# phase_and_amplifier_ssb.net
KiCad netlist of a schematic drawn in EAGLE
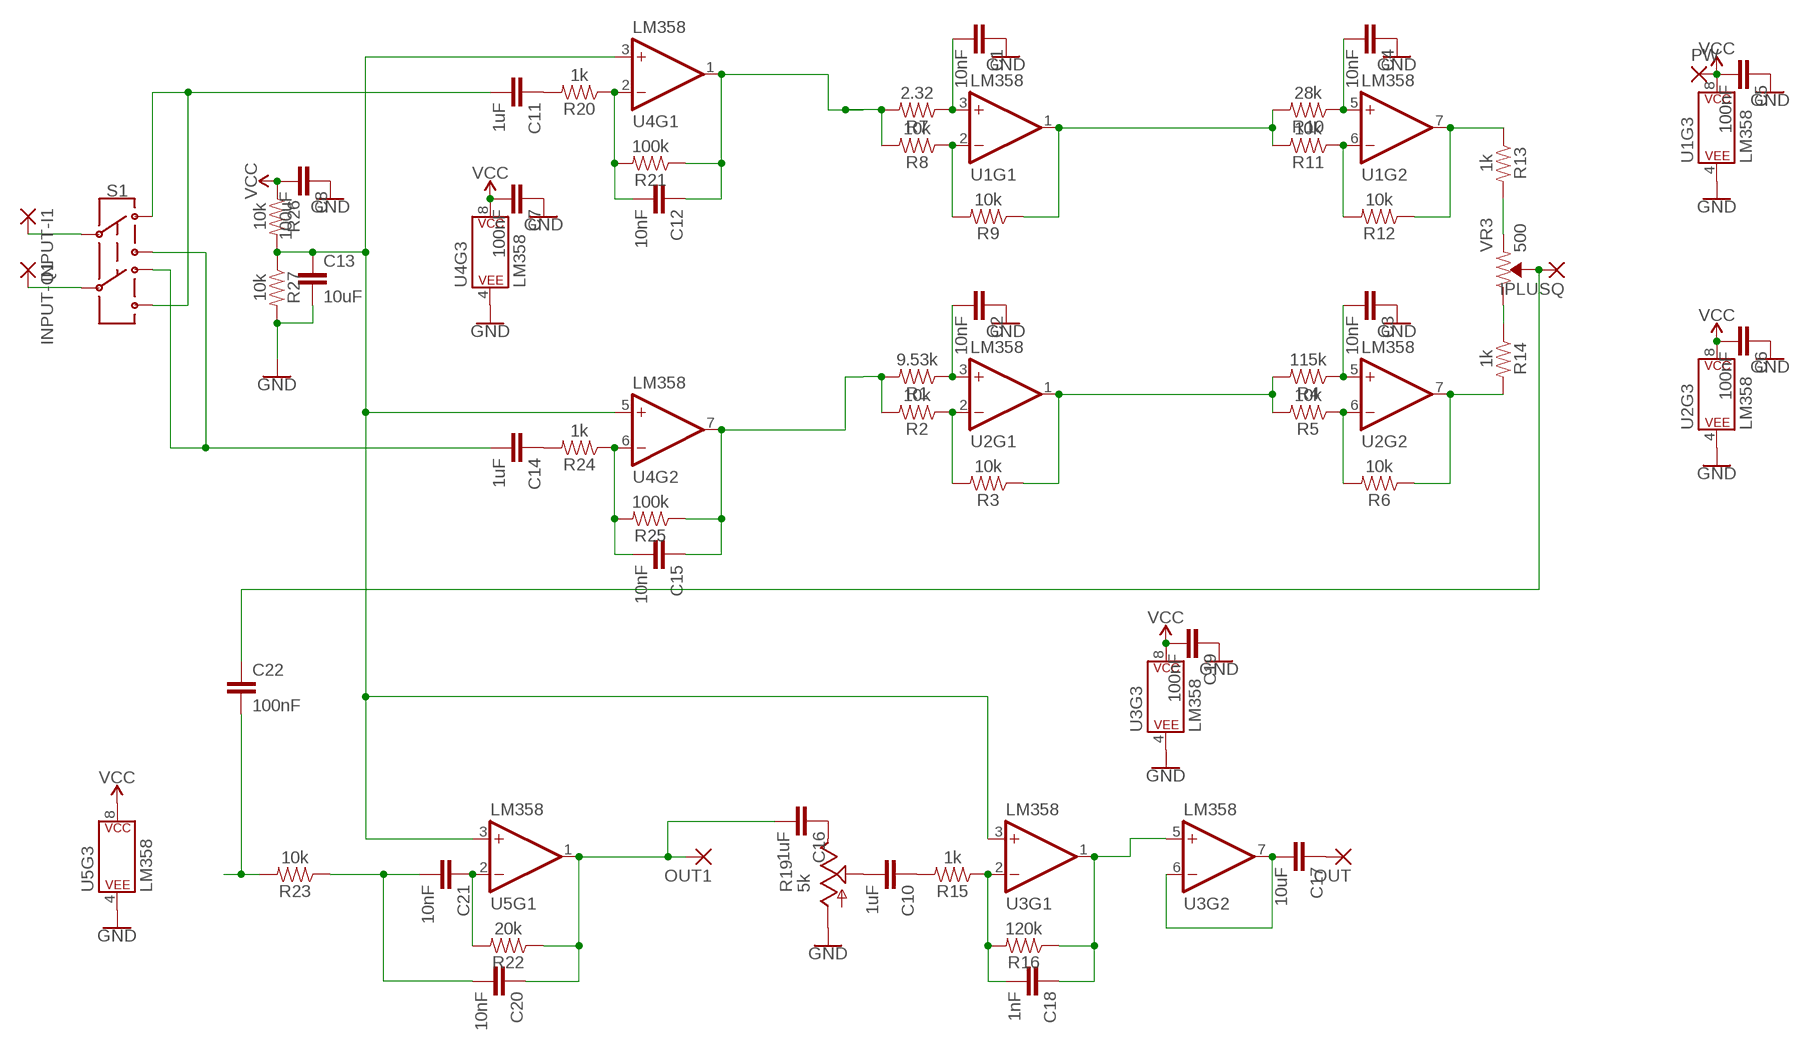
[diagram p0: schematic, sheet 1]

(export (version "E")
  (design (tool "Eeschema 10.0.6"))
  (components
    (comp (ref "C1")
      (value "10nF")
      (footprint "eagle-import:C5B3.5")
      (libsource (lib "eagle-import") (part "C5/3.5"))
    )
    (comp (ref "C2")
      (value "10nF")
      (footprint "eagle-import:C5B3.5")
      (libsource (lib "eagle-import") (part "C5/3.5"))
    )
    (comp (ref "C3")
      (value "10nF")
      (footprint "eagle-import:C5B3.5")
      (libsource (lib "eagle-import") (part "C5/3.5"))
    )
    (comp (ref "C4")
      (value "10nF")
      (footprint "eagle-import:C5B3.5")
      (libsource (lib "eagle-import") (part "C5/3.5"))
    )
    (comp (ref "C5")
      (value "100nF")
      (footprint "eagle-import:C5B3.5")
      (libsource (lib "eagle-import") (part "C5/3.5"))
    )
    (comp (ref "C6")
      (value "100nF")
      (footprint "eagle-import:C5B3.5")
      (libsource (lib "eagle-import") (part "C5/3.5"))
    )
    (comp (ref "C7")
      (value "100nF")
      (footprint "eagle-import:C5B3.5")
      (libsource (lib "eagle-import") (part "C5/3.5"))
    )
    (comp (ref "C8")
      (value "100uF")
      (footprint "eagle-import:C5B3.5")
      (libsource (lib "eagle-import") (part "C5/3.5"))
    )
    (comp (ref "C10")
      (value "1uF")
      (footprint "eagle-import:C5B3.5")
      (libsource (lib "eagle-import") (part "C5/3.5"))
    )
    (comp (ref "C11")
      (value "1uF")
      (footprint "eagle-import:C5B3.5")
      (libsource (lib "eagle-import") (part "C5/3.5"))
    )
    (comp (ref "C12")
      (value "10nF")
      (footprint "eagle-import:C5B3.5")
      (libsource (lib "eagle-import") (part "C5/3.5"))
    )
    (comp (ref "C13")
      (value "10uF")
      (footprint "eagle-import:C5B3.5")
      (libsource (lib "eagle-import") (part "C5/3.5"))
    )
    (comp (ref "C14")
      (value "1uF")
      (footprint "eagle-import:C5B3.5")
      (libsource (lib "eagle-import") (part "C5/3.5"))
    )
    (comp (ref "C15")
      (value "10nF")
      (footprint "eagle-import:C5B3.5")
      (libsource (lib "eagle-import") (part "C5/3.5"))
    )
    (comp (ref "C16")
      (value "1uF")
      (footprint "eagle-import:C5B3.5")
      (libsource (lib "eagle-import") (part "C5/3.5"))
    )
    (comp (ref "C17")
      (value "10uF")
      (footprint "eagle-import:C5B3.5")
      (libsource (lib "eagle-import") (part "C5/3.5"))
    )
    (comp (ref "C18")
      (value "1nF")
      (footprint "eagle-import:C5B3.5")
      (libsource (lib "eagle-import") (part "C5/3.5"))
    )
    (comp (ref "C19")
      (value "100nF")
      (footprint "eagle-import:C5B3.5")
      (libsource (lib "eagle-import") (part "C5/3.5"))
    )
    (comp (ref "C20")
      (value "10nF")
      (footprint "eagle-import:C5B3.5")
      (libsource (lib "eagle-import") (part "C5/3.5"))
    )
    (comp (ref "C21")
      (value "10nF")
      (footprint "eagle-import:C5B3.5")
      (libsource (lib "eagle-import") (part "C5/3.5"))
    )
    (comp (ref "C22")
      (value "100nF")
      (footprint "eagle-import:C5B3.5")
      (libsource (lib "eagle-import") (part "C5/3.5"))
    )
    (comp (ref "INPUT-I1")
      (value "2,54/1,1")
      (footprint "eagle-import:2,54_1,1")
      (libsource (lib "eagle-import") (part "2,54/1,1"))
    )
    (comp (ref "INPUT-Q1")
      (value "2,54/1,1")
      (footprint "eagle-import:2,54_1,1")
      (libsource (lib "eagle-import") (part "2,54/1,1"))
    )
    (comp (ref "IPLUSQ")
      (value "2,54/1,1")
      (footprint "eagle-import:2,54_1,1")
      (libsource (lib "eagle-import") (part "2,54/1,1"))
    )
    (comp (ref "OUT")
      (value "2,54/1,1")
      (footprint "eagle-import:2,54_1,1")
      (libsource (lib "eagle-import") (part "2,54/1,1"))
    )
    (comp (ref "OUT1")
      (value "2,54/1,1")
      (footprint "eagle-import:2,54_1,1")
      (libsource (lib "eagle-import") (part "2,54/1,1"))
    )
    (comp (ref "PW")
      (value "2,54/1,1")
      (footprint "eagle-import:2,54_1,1")
      (libsource (lib "eagle-import") (part "2,54/1,1"))
    )
    (comp (ref "R1")
      (value "9.53k")
      (footprint "eagle-import:AXIAL-0.3")
      (libsource (lib "eagle-import") (part "1KOHM-HORIZ-1/4W-1%"))
    )
    (comp (ref "R2")
      (value "10k")
      (footprint "eagle-import:AXIAL-0.3")
      (libsource (lib "eagle-import") (part "1KOHM-HORIZ-1/4W-1%"))
    )
    (comp (ref "R3")
      (value "10k")
      (footprint "eagle-import:AXIAL-0.3")
      (libsource (lib "eagle-import") (part "1KOHM-HORIZ-1/4W-1%"))
    )
    (comp (ref "R4")
      (value "115k")
      (footprint "eagle-import:AXIAL-0.3")
      (libsource (lib "eagle-import") (part "1KOHM-HORIZ-1/4W-1%"))
    )
    (comp (ref "R5")
      (value "10k")
      (footprint "eagle-import:AXIAL-0.3")
      (libsource (lib "eagle-import") (part "1KOHM-HORIZ-1/4W-1%"))
    )
    (comp (ref "R6")
      (value "10k")
      (footprint "eagle-import:AXIAL-0.3")
      (libsource (lib "eagle-import") (part "1KOHM-HORIZ-1/4W-1%"))
    )
    (comp (ref "R7")
      (value "2.32")
      (footprint "eagle-import:AXIAL-0.3")
      (libsource (lib "eagle-import") (part "1KOHM-HORIZ-1/4W-1%"))
    )
    (comp (ref "R8")
      (value "10k")
      (footprint "eagle-import:AXIAL-0.3")
      (libsource (lib "eagle-import") (part "1KOHM-HORIZ-1/4W-1%"))
    )
    (comp (ref "R9")
      (value "10k")
      (footprint "eagle-import:AXIAL-0.3")
      (libsource (lib "eagle-import") (part "1KOHM-HORIZ-1/4W-1%"))
    )
    (comp (ref "R10")
      (value "28k")
      (footprint "eagle-import:AXIAL-0.3")
      (libsource (lib "eagle-import") (part "1KOHM-HORIZ-1/4W-1%"))
    )
    (comp (ref "R11")
      (value "10k")
      (footprint "eagle-import:AXIAL-0.3")
      (libsource (lib "eagle-import") (part "1KOHM-HORIZ-1/4W-1%"))
    )
    (comp (ref "R12")
      (value "10k")
      (footprint "eagle-import:AXIAL-0.3")
      (libsource (lib "eagle-import") (part "1KOHM-HORIZ-1/4W-1%"))
    )
    (comp (ref "R13")
      (value "1k")
      (footprint "eagle-import:AXIAL-0.3")
      (libsource (lib "eagle-import") (part "1KOHM-HORIZ-1/4W-1%"))
    )
    (comp (ref "R14")
      (value "1k")
      (footprint "eagle-import:AXIAL-0.3")
      (libsource (lib "eagle-import") (part "1KOHM-HORIZ-1/4W-1%"))
    )
    (comp (ref "R15")
      (value "1k")
      (footprint "eagle-import:AXIAL-0.3")
      (libsource (lib "eagle-import") (part "1KOHM-HORIZ-1/4W-1%"))
    )
    (comp (ref "R16")
      (value "120k")
      (footprint "eagle-import:AXIAL-0.3")
      (libsource (lib "eagle-import") (part "1KOHM-HORIZ-1/4W-1%"))
    )
    (comp (ref "R19")
      (value "5k")
      (footprint "eagle-import:B25V")
      (libsource (lib "eagle-import") (part "TRIM_US-B25V"))
    )
    (comp (ref "R20")
      (value "1k")
      (footprint "eagle-import:AXIAL-0.3")
      (libsource (lib "eagle-import") (part "1KOHM-HORIZ-1/4W-1%"))
    )
    (comp (ref "R21")
      (value "100k")
      (footprint "eagle-import:AXIAL-0.3")
      (libsource (lib "eagle-import") (part "1KOHM-HORIZ-1/4W-1%"))
    )
    (comp (ref "R22")
      (value "20k")
      (footprint "eagle-import:AXIAL-0.3")
      (libsource (lib "eagle-import") (part "1KOHM-HORIZ-1/4W-1%"))
    )
    (comp (ref "R23")
      (value "10k")
      (footprint "eagle-import:AXIAL-0.3")
      (libsource (lib "eagle-import") (part "1KOHM-HORIZ-1/4W-1%"))
    )
    (comp (ref "R24")
      (value "1k")
      (footprint "eagle-import:AXIAL-0.3")
      (libsource (lib "eagle-import") (part "1KOHM-HORIZ-1/4W-1%"))
    )
    (comp (ref "R25")
      (value "100k")
      (footprint "eagle-import:AXIAL-0.3")
      (libsource (lib "eagle-import") (part "1KOHM-HORIZ-1/4W-1%"))
    )
    (comp (ref "R26")
      (value "10k")
      (footprint "eagle-import:AXIAL-0.3")
      (libsource (lib "eagle-import") (part "1KOHM-HORIZ-1/4W-1%"))
    )
    (comp (ref "R27")
      (value "10k")
      (footprint "eagle-import:AXIAL-0.3")
      (libsource (lib "eagle-import") (part "1KOHM-HORIZ-1/4W-1%"))
    )
    (comp (ref "S1")
      (value "SWITCH-DPDT-PTH-GPI-152-3013")
      (footprint "eagle-import:SWITCH_DPDT_PTH_GPI-152-3013")
      (libsource (lib "eagle-import") (part "SWITCH-DPDT-PTH-GPI-152-3013"))
    )
    (comp (ref "U1")
      (value "LM358")
      (footprint "eagle-import:DIP08")
      (libsource (lib "eagle-import") (part "LM358"))
    )
    (comp (ref "U2")
      (value "LM358")
      (footprint "eagle-import:DIP08")
      (libsource (lib "eagle-import") (part "LM358"))
    )
    (comp (ref "U3")
      (value "LM358")
      (footprint "eagle-import:DIP08")
      (libsource (lib "eagle-import") (part "LM358"))
    )
    (comp (ref "U4")
      (value "LM358")
      (footprint "eagle-import:DIP08")
      (libsource (lib "eagle-import") (part "LM358"))
    )
    (comp (ref "U5")
      (value "LM358")
      (footprint "eagle-import:DIP08")
      (libsource (lib "eagle-import") (part "LM358"))
    )
    (comp (ref "VR3")
      (value "500")
      (footprint "eagle-import:TRIMPOT-PTH-3386U")
      (libsource (lib "eagle-import") (part "TRIMPOT-PTH-10MM-KNOB-1/2W-10%"))
    )
  )
  (nets
    (net (code "1") (name "GND") (class "Default")
      (node (ref "C1") (pin "1") (pinfunction "1_1") (pintype "passive"))
      (node (ref "C13") (pin "2") (pinfunction "2_2") (pintype "passive"))
      (node (ref "C19") (pin "1") (pinfunction "1_1") (pintype "passive"))
      (node (ref "C2") (pin "1") (pinfunction "1_1") (pintype "passive"))
      (node (ref "C3") (pin "1") (pinfunction "1_1") (pintype "passive"))
      (node (ref "C4") (pin "1") (pinfunction "1_1") (pintype "passive"))
      (node (ref "C5") (pin "1") (pinfunction "1_1") (pintype "passive"))
      (node (ref "C6") (pin "1") (pinfunction "1_1") (pintype "passive"))
      (node (ref "C7") (pin "1") (pinfunction "1_1") (pintype "passive"))
      (node (ref "C8") (pin "1") (pinfunction "1_1") (pintype "passive"))
      (node (ref "R19") (pin "A") (pinfunction "A_A") (pintype "passive"))
      (node (ref "R27") (pin "P$2") (pinfunction "2_P$2") (pintype "passive"))
      (node (ref "U1") (pin "4") (pinfunction "P$V-_4") (pintype "bidirectional"))
      (node (ref "U2") (pin "4") (pinfunction "P$V-_4") (pintype "bidirectional"))
      (node (ref "U3") (pin "4") (pinfunction "P$V-_4") (pintype "bidirectional"))
      (node (ref "U4") (pin "4") (pinfunction "P$V-_4") (pintype "bidirectional"))
      (node (ref "U5") (pin "4") (pinfunction "P$V-_4") (pintype "bidirectional"))
    )
    (net (code "2") (name "Net-(C10-Pad2)") (class "Default")
      (node (ref "C10") (pin "2") (pinfunction "2_2") (pintype "passive"))
      (node (ref "R19") (pin "S") (pinfunction "S_S") (pintype "passive"))
    )
    (net (code "3") (name "Net-(C16-Pad1)") (class "Default")
      (node (ref "C16") (pin "1") (pinfunction "1_1") (pintype "passive"))
      (node (ref "R19") (pin "E") (pinfunction "E_E") (pintype "passive"))
    )
    (net (code "4") (name "Net-(INPUT-I1-P)") (class "Default")
      (node (ref "INPUT-I1") (pin "1") (pinfunction "P_1") (pintype "passive"))
      (node (ref "S1") (pin "C@1") (pinfunction "2_C@1") (pintype "bidirectional"))
    )
    (net (code "5") (name "Net-(INPUT-Q1-P)") (class "Default")
      (node (ref "INPUT-Q1") (pin "1") (pinfunction "P_1") (pintype "passive"))
      (node (ref "S1") (pin "C@2") (pinfunction "5_C@2") (pintype "bidirectional"))
    )
    (net (code "6") (name "Net-(IPLUSQ-P)") (class "Default")
      (node (ref "C22") (pin "1") (pinfunction "1_1") (pintype "passive"))
      (node (ref "IPLUSQ") (pin "1") (pinfunction "P_1") (pintype "passive"))
      (node (ref "VR3") (pin "2") (pinfunction "WIPER_2") (pintype "passive"))
    )
    (net (code "7") (name "Net-(OUT-P)") (class "Default")
      (node (ref "C17") (pin "1") (pinfunction "1_1") (pintype "passive"))
      (node (ref "OUT") (pin "1") (pinfunction "P_1") (pintype "passive"))
    )
    (net (code "8") (name "Net-(OUT1-P)") (class "Default")
      (node (ref "C16") (pin "2") (pinfunction "2_2") (pintype "passive"))
      (node (ref "C20") (pin "1") (pinfunction "1_1") (pintype "passive"))
      (node (ref "OUT1") (pin "1") (pinfunction "P_1") (pintype "passive"))
      (node (ref "R22") (pin "P$1") (pinfunction "1_P$1") (pintype "passive"))
      (node (ref "U5") (pin "1") (pinfunction "OUT_1") (pintype "output"))
    )
    (net (code "9") (name "Net-(R1-1)") (class "Default")
      (node (ref "C2") (pin "2") (pinfunction "2_2") (pintype "passive"))
      (node (ref "R1") (pin "P$1") (pinfunction "1_P$1") (pintype "passive"))
      (node (ref "U2") (pin "3") (pinfunction "+IN_3") (pintype "input"))
    )
    (net (code "10") (name "Net-(R1-2)") (class "Default")
      (node (ref "C15") (pin "1") (pinfunction "1_1") (pintype "passive"))
      (node (ref "R1") (pin "P$2") (pinfunction "2_P$2") (pintype "passive"))
      (node (ref "R2") (pin "P$2") (pinfunction "2_P$2") (pintype "passive"))
      (node (ref "R25") (pin "P$1") (pinfunction "1_P$1") (pintype "passive"))
      (node (ref "U4") (pin "7") (pinfunction "OUT_7") (pintype "output"))
    )
    (net (code "11") (name "Net-(R2-1)") (class "Default")
      (node (ref "R2") (pin "P$1") (pinfunction "1_P$1") (pintype "passive"))
      (node (ref "R3") (pin "P$2") (pinfunction "2_P$2") (pintype "passive"))
      (node (ref "U2") (pin "2") (pinfunction "-IN_2") (pintype "input"))
    )
    (net (code "12") (name "Net-(R3-1)") (class "Default")
      (node (ref "R3") (pin "P$1") (pinfunction "1_P$1") (pintype "passive"))
      (node (ref "R4") (pin "P$2") (pinfunction "2_P$2") (pintype "passive"))
      (node (ref "R5") (pin "P$2") (pinfunction "2_P$2") (pintype "passive"))
      (node (ref "U2") (pin "1") (pinfunction "OUT_1") (pintype "output"))
    )
    (net (code "13") (name "Net-(R4-1)") (class "Default")
      (node (ref "C3") (pin "2") (pinfunction "2_2") (pintype "passive"))
      (node (ref "R4") (pin "P$1") (pinfunction "1_P$1") (pintype "passive"))
      (node (ref "U2") (pin "5") (pinfunction "+IN_5") (pintype "input"))
    )
    (net (code "14") (name "Net-(R5-1)") (class "Default")
      (node (ref "R5") (pin "P$1") (pinfunction "1_P$1") (pintype "passive"))
      (node (ref "R6") (pin "P$2") (pinfunction "2_P$2") (pintype "passive"))
      (node (ref "U2") (pin "6") (pinfunction "-IN_6") (pintype "input"))
    )
    (net (code "15") (name "Net-(R7-1)") (class "Default")
      (node (ref "C1") (pin "2") (pinfunction "2_2") (pintype "passive"))
      (node (ref "R7") (pin "P$1") (pinfunction "1_P$1") (pintype "passive"))
      (node (ref "U1") (pin "3") (pinfunction "+IN_3") (pintype "input"))
    )
    (net (code "16") (name "Net-(R8-1)") (class "Default")
      (node (ref "R8") (pin "P$1") (pinfunction "1_P$1") (pintype "passive"))
      (node (ref "R9") (pin "P$2") (pinfunction "2_P$2") (pintype "passive"))
      (node (ref "U1") (pin "2") (pinfunction "-IN_2") (pintype "input"))
    )
    (net (code "17") (name "Net-(R10-1)") (class "Default")
      (node (ref "C4") (pin "2") (pinfunction "2_2") (pintype "passive"))
      (node (ref "R10") (pin "P$1") (pinfunction "1_P$1") (pintype "passive"))
      (node (ref "U1") (pin "5") (pinfunction "+IN_5") (pintype "input"))
    )
    (net (code "18") (name "Net-(R10-2)") (class "Default")
      (node (ref "R10") (pin "P$2") (pinfunction "2_P$2") (pintype "passive"))
      (node (ref "R11") (pin "P$2") (pinfunction "2_P$2") (pintype "passive"))
      (node (ref "R9") (pin "P$1") (pinfunction "1_P$1") (pintype "passive"))
      (node (ref "U1") (pin "1") (pinfunction "OUT_1") (pintype "output"))
    )
    (net (code "19") (name "Net-(R11-1)") (class "Default")
      (node (ref "R11") (pin "P$1") (pinfunction "1_P$1") (pintype "passive"))
      (node (ref "R12") (pin "P$2") (pinfunction "2_P$2") (pintype "passive"))
      (node (ref "U1") (pin "6") (pinfunction "-IN_6") (pintype "input"))
    )
    (net (code "20") (name "Net-(R12-1)") (class "Default")
      (node (ref "R12") (pin "P$1") (pinfunction "1_P$1") (pintype "passive"))
      (node (ref "R13") (pin "P$1") (pinfunction "1_P$1") (pintype "passive"))
      (node (ref "U1") (pin "7") (pinfunction "OUT_7") (pintype "output"))
    )
    (net (code "21") (name "Net-(R13-2)") (class "Default")
      (node (ref "R13") (pin "P$2") (pinfunction "2_P$2") (pintype "passive"))
      (node (ref "VR3") (pin "1") (pinfunction "CCW_1") (pintype "passive"))
    )
    (net (code "22") (name "Net-(R14-1)") (class "Default")
      (node (ref "R14") (pin "P$1") (pinfunction "1_P$1") (pintype "passive"))
      (node (ref "VR3") (pin "3") (pinfunction "CW_3") (pintype "passive"))
    )
    (net (code "23") (name "Net-(R14-2)") (class "Default")
      (node (ref "R14") (pin "P$2") (pinfunction "2_P$2") (pintype "passive"))
      (node (ref "R6") (pin "P$1") (pinfunction "1_P$1") (pintype "passive"))
      (node (ref "U2") (pin "7") (pinfunction "OUT_7") (pintype "output"))
    )
    (net (code "24") (name "Net-(R15-1)") (class "Default")
      (node (ref "C18") (pin "2") (pinfunction "2_2") (pintype "passive"))
      (node (ref "R15") (pin "P$1") (pinfunction "1_P$1") (pintype "passive"))
      (node (ref "R16") (pin "P$2") (pinfunction "2_P$2") (pintype "passive"))
      (node (ref "U3") (pin "2") (pinfunction "-IN_2") (pintype "input"))
    )
    (net (code "25") (name "Net-(R15-2)") (class "Default")
      (node (ref "C10") (pin "1") (pinfunction "1_1") (pintype "passive"))
      (node (ref "R15") (pin "P$2") (pinfunction "2_P$2") (pintype "passive"))
    )
    (net (code "26") (name "Net-(R16-1)") (class "Default")
      (node (ref "C18") (pin "1") (pinfunction "1_1") (pintype "passive"))
      (node (ref "R16") (pin "P$1") (pinfunction "1_P$1") (pintype "passive"))
      (node (ref "U3") (pin "1") (pinfunction "OUT_1") (pintype "output"))
      (node (ref "U3") (pin "5") (pinfunction "+IN_5") (pintype "input"))
    )
    (net (code "27") (name "Net-(R20-1)") (class "Default")
      (node (ref "C12") (pin "2") (pinfunction "2_2") (pintype "passive"))
      (node (ref "R20") (pin "P$1") (pinfunction "1_P$1") (pintype "passive"))
      (node (ref "R21") (pin "P$2") (pinfunction "2_P$2") (pintype "passive"))
      (node (ref "U4") (pin "2") (pinfunction "-IN_2") (pintype "input"))
    )
    (net (code "28") (name "Net-(R20-2)") (class "Default")
      (node (ref "C11") (pin "1") (pinfunction "1_1") (pintype "passive"))
      (node (ref "R20") (pin "P$2") (pinfunction "2_P$2") (pintype "passive"))
    )
    (net (code "29") (name "Net-(R21-1)") (class "Default")
      (node (ref "C12") (pin "1") (pinfunction "1_1") (pintype "passive"))
      (node (ref "R21") (pin "P$1") (pinfunction "1_P$1") (pintype "passive"))
      (node (ref "R7") (pin "P$2") (pinfunction "2_P$2") (pintype "passive"))
      (node (ref "R8") (pin "P$2") (pinfunction "2_P$2") (pintype "passive"))
      (node (ref "U4") (pin "1") (pinfunction "OUT_1") (pintype "output"))
    )
    (net (code "30") (name "Net-(R22-2)") (class "Default")
      (node (ref "C21") (pin "1") (pinfunction "1_1") (pintype "passive"))
      (node (ref "R22") (pin "P$2") (pinfunction "2_P$2") (pintype "passive"))
      (node (ref "U5") (pin "2") (pinfunction "-IN_2") (pintype "input"))
    )
    (net (code "31") (name "Net-(R23-1)") (class "Default")
      (node (ref "C20") (pin "2") (pinfunction "2_2") (pintype "passive"))
      (node (ref "C21") (pin "2") (pinfunction "2_2") (pintype "passive"))
      (node (ref "R23") (pin "P$1") (pinfunction "1_P$1") (pintype "passive"))
    )
    (net (code "32") (name "Net-(R23-2)") (class "Default")
      (node (ref "C22") (pin "2") (pinfunction "2_2") (pintype "passive"))
      (node (ref "R23") (pin "P$2") (pinfunction "2_P$2") (pintype "passive"))
    )
    (net (code "33") (name "Net-(R24-1)") (class "Default")
      (node (ref "C15") (pin "2") (pinfunction "2_2") (pintype "passive"))
      (node (ref "R24") (pin "P$1") (pinfunction "1_P$1") (pintype "passive"))
      (node (ref "R25") (pin "P$2") (pinfunction "2_P$2") (pintype "passive"))
      (node (ref "U4") (pin "6") (pinfunction "-IN_6") (pintype "input"))
    )
    (net (code "34") (name "Net-(R24-2)") (class "Default")
      (node (ref "C14") (pin "1") (pinfunction "1_1") (pintype "passive"))
      (node (ref "R24") (pin "P$2") (pinfunction "2_P$2") (pintype "passive"))
    )
    (net (code "35") (name "Net-(R26-2)") (class "Default")
      (node (ref "C13") (pin "1") (pinfunction "1_1") (pintype "passive"))
      (node (ref "R26") (pin "P$2") (pinfunction "2_P$2") (pintype "passive"))
      (node (ref "R27") (pin "P$1") (pinfunction "1_P$1") (pintype "passive"))
      (node (ref "U3") (pin "3") (pinfunction "+IN_3") (pintype "input"))
      (node (ref "U4") (pin "3") (pinfunction "+IN_3") (pintype "input"))
      (node (ref "U4") (pin "5") (pinfunction "+IN_5") (pintype "input"))
      (node (ref "U5") (pin "3") (pinfunction "+IN_3") (pintype "input"))
    )
    (net (code "36") (name "Net-(S1-1)") (class "Default")
      (node (ref "C11") (pin "2") (pinfunction "2_2") (pintype "passive"))
      (node (ref "S1") (pin "10") (pinfunction "1_10") (pintype "bidirectional"))
      (node (ref "S1") (pin "21") (pinfunction "6_21") (pintype "bidirectional"))
    )
    (net (code "37") (name "Net-(S1-3)") (class "Default")
      (node (ref "C14") (pin "2") (pinfunction "2_2") (pintype "passive"))
      (node (ref "S1") (pin "11") (pinfunction "4_11") (pintype "bidirectional"))
      (node (ref "S1") (pin "20") (pinfunction "3_20") (pintype "bidirectional"))
    )
    (net (code "38") (name "Net-(U3B--IN)") (class "Default")
      (node (ref "C17") (pin "2") (pinfunction "2_2") (pintype "passive"))
      (node (ref "U3") (pin "6") (pinfunction "-IN_6") (pintype "input"))
      (node (ref "U3") (pin "7") (pinfunction "OUT_7") (pintype "output"))
    )
    (net (code "39") (name "VCC") (class "Default")
      (node (ref "C19") (pin "2") (pinfunction "2_2") (pintype "passive"))
      (node (ref "C5") (pin "2") (pinfunction "2_2") (pintype "passive"))
      (node (ref "C6") (pin "2") (pinfunction "2_2") (pintype "passive"))
      (node (ref "C7") (pin "2") (pinfunction "2_2") (pintype "passive"))
      (node (ref "C8") (pin "2") (pinfunction "2_2") (pintype "passive"))
      (node (ref "PW") (pin "1") (pinfunction "P_1") (pintype "passive"))
      (node (ref "R26") (pin "P$1") (pinfunction "1_P$1") (pintype "passive"))
      (node (ref "U1") (pin "8") (pinfunction "P$V+_8") (pintype "bidirectional"))
      (node (ref "U2") (pin "8") (pinfunction "P$V+_8") (pintype "bidirectional"))
      (node (ref "U3") (pin "8") (pinfunction "P$V+_8") (pintype "bidirectional"))
      (node (ref "U4") (pin "8") (pinfunction "P$V+_8") (pintype "bidirectional"))
      (node (ref "U5") (pin "8") (pinfunction "P$V+_8") (pintype "bidirectional"))
    )
  )
)
